# POWER.net
KiCad netlist of a schematic drawn in Altium Designer
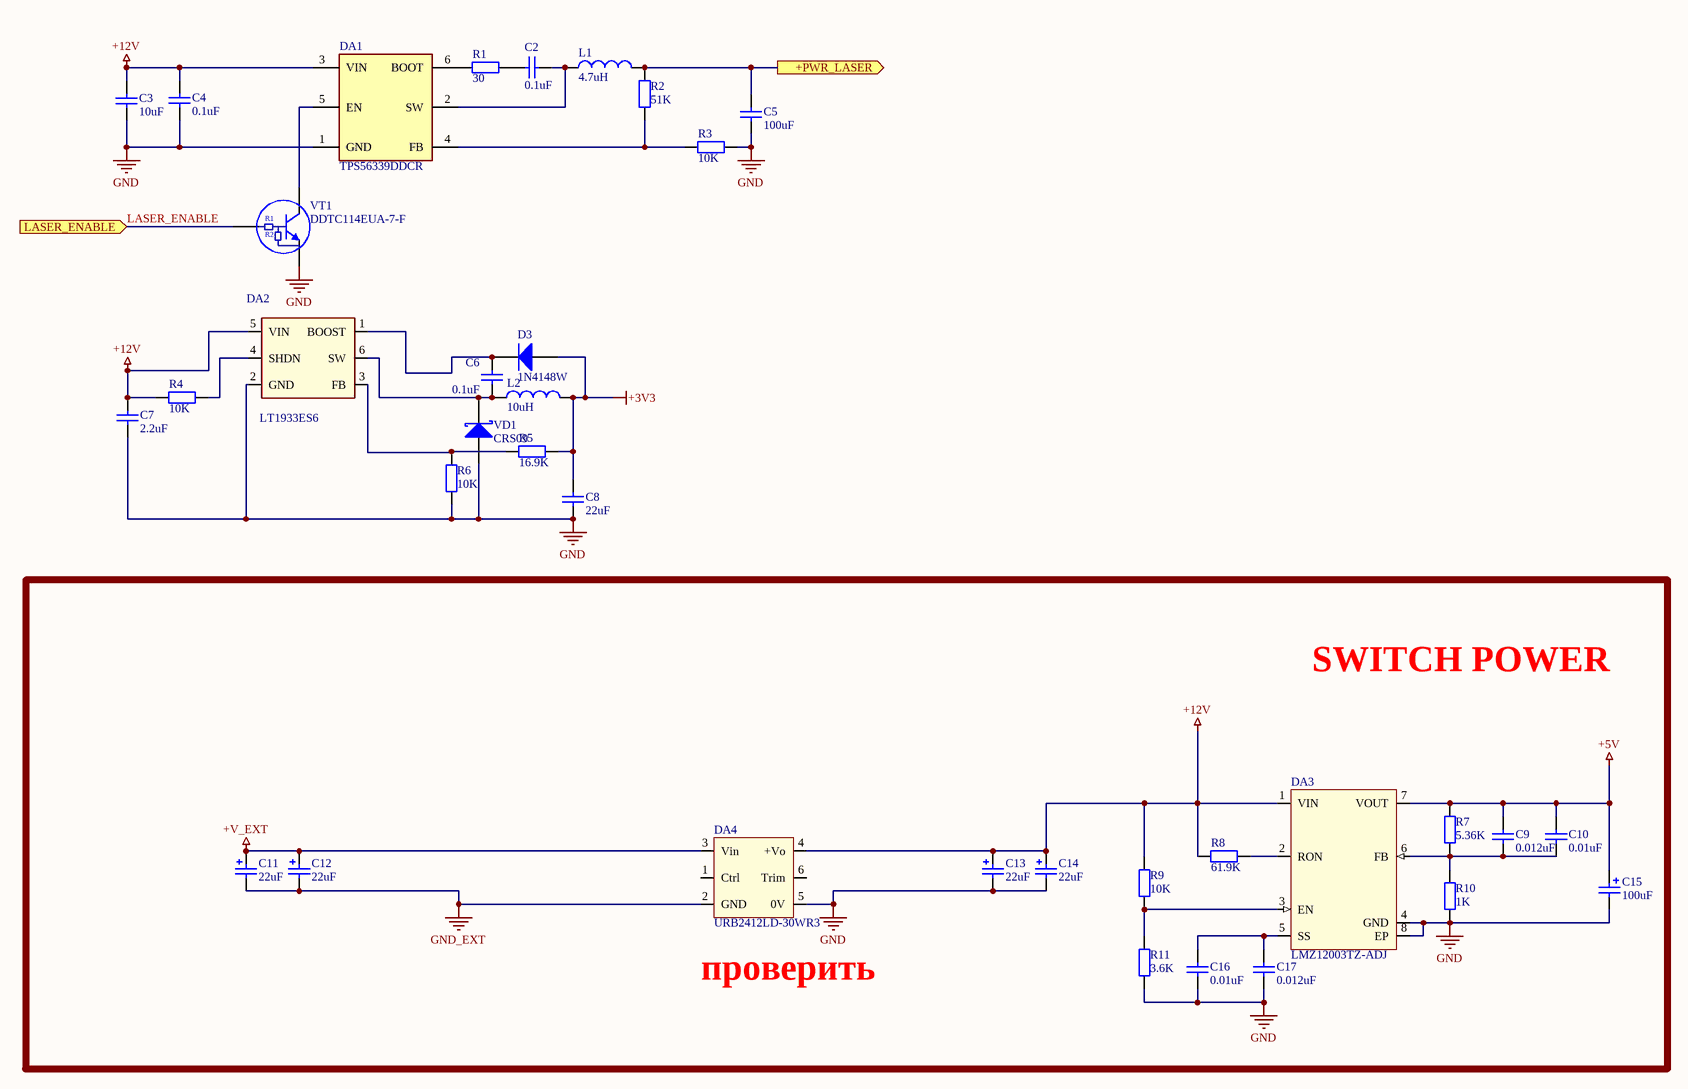
[diagram p0: POWER.SchDoc]

(export (version "E")
  (design (tool "Eeschema 10.0.6"))
  (components
    (comp (ref "C2")
      (value "0.1uF")
      (footprint "C0603")
      (description "Ceramic Capacitor")
      (fields (field (name "Comment") "C0603-0.1uF-50V-X7R"))
      (libsource (lib "Capacitors") (part "C0603-0.1uF-50V-X7R"))
    )
    (comp (ref "C3")
      (value "10uF")
      (footprint "C1210")
      (description "Ceramic Capacitor")
      (fields (field (name "Comment") "C1210-10uF-50V-X7R"))
      (libsource (lib "Capacitors") (part "C1210-10uF-50V-X7R"))
    )
    (comp (ref "C4")
      (value "0.1uF")
      (footprint "C0603")
      (description "Ceramic Capacitor")
      (fields (field (name "Comment") "C0603-0.1uF-50V-X7R"))
      (libsource (lib "Capacitors") (part "C0603-0.1uF-50V-X7R"))
    )
    (comp (ref "C5")
      (value "100uF")
      (footprint "C1206")
      (description "Ceramic Capacitor")
      (fields (field (name "Comment") "C1206-100uF-10V-X5R"))
      (libsource (lib "Capacitors") (part "C1206-100uF-10V-X5R"))
    )
    (comp (ref "C6")
      (value "0.1uF")
      (footprint "C0603")
      (description "Ceramic Capacitor")
      (fields (field (name "Comment") "C0603-0.1uF-50V-X7R"))
      (libsource (lib "Capacitors_SpekrtAT") (part "C0603-0.1uF-50V-X7R"))
    )
    (comp (ref "C7")
      (value "2.2uF")
      (footprint "C1206")
      (description "Ceramic Capacitor")
      (fields (field (name "Comment") "C1206-2.2uF-50V-X7R"))
      (libsource (lib "Capacitors") (part "C1206-2.2uF-50V-X7R"))
    )
    (comp (ref "C8")
      (value "22uF")
      (footprint "C0805")
      (description "Ceramic Capacitor")
      (fields (field (name "Comment") "C0805-22uF-10V-X5R"))
      (libsource (lib "Capacitors_SpekrtAT") (part "C0805-22uF-10V-X5R"))
    )
    (comp (ref "C9")
      (value "0.012uF")
      (footprint "C0603")
      (description "Ceramic Capacitor")
      (fields (field (name "Comment") "C0603-0.012uF-50V-X7R"))
      (libsource (lib "Capacitors_SpekrtAT") (part "C0603-0.012uF-50V-X7R"))
    )
    (comp (ref "C10")
      (value "0.01uF")
      (footprint "C0603")
      (description "Ceramic Capacitor")
      (fields (field (name "Comment") "C0603-0.01uF-50V-X7R"))
      (libsource (lib "Capacitors_SpekrtAT") (part "C0603-0.01uF-50V-X7R"))
    )
    (comp (ref "C11")
      (value "22uF")
      (footprint "CTD")
      (description "Tantalum Capacitor")
      (fields (field (name "Comment") "CTD-22uF-35V"))
      (libsource (lib "Capacitors_SpekrtAT") (part "CTD-22uF-35V"))
    )
    (comp (ref "C12")
      (value "22uF")
      (footprint "CTD")
      (description "Tantalum Capacitor")
      (fields (field (name "Comment") "CTD-22uF-35V"))
      (libsource (lib "Capacitors_SpekrtAT") (part "CTD-22uF-35V"))
    )
    (comp (ref "C13")
      (value "22uF")
      (footprint "CTD")
      (description "Tantalum Capacitor")
      (fields (field (name "Comment") "CTD-22uF-35V"))
      (libsource (lib "Capacitors_SpekrtAT") (part "CTD-22uF-35V"))
    )
    (comp (ref "C14")
      (value "22uF")
      (footprint "CTD")
      (description "Tantalum Capacitor")
      (fields (field (name "Comment") "CTD-22uF-35V"))
      (libsource (lib "Capacitors_SpekrtAT") (part "CTD-22uF-35V"))
    )
    (comp (ref "C15")
      (value "100uF")
      (footprint "CTD")
      (description "Tantalum Capacitor")
      (fields (field (name "Comment") "CTD-100uF-16V"))
      (libsource (lib "Capacitors_SpekrtAT") (part "CTD-100uF-16V"))
    )
    (comp (ref "C16")
      (value "0.01uF")
      (footprint "C0603")
      (description "Ceramic Capacitor")
      (fields (field (name "Comment") "C0603-0.01uF-50V-X7R"))
      (libsource (lib "Capacitors_SpekrtAT") (part "C0603-0.01uF-50V-X7R"))
    )
    (comp (ref "C17")
      (value "0.012uF")
      (footprint "C0603")
      (description "Ceramic Capacitor")
      (fields (field (name "Comment") "C0603-0.012uF-50V-X7R"))
      (libsource (lib "Capacitors_SpekrtAT") (part "C0603-0.012uF-50V-X7R"))
    )
    (comp (ref "D3")
      (value "1N4148W")
      (footprint "SOD323")
      (description "Diode")
      (libsource (lib "Diodes_SpekrtAT") (part "1N4148W"))
    )
    (comp (ref "DA1")
      (value "TPS56339DDCR")
      (footprint "SOT23-6")
      (description "4.5-V to 24-V Input, 3-A Output Synchronous Buck Converter")
      (libsource (lib "ICs") (part "TPS56339DDCR"))
    )
    (comp (ref "DA2")
      (value "LT1933ES6")
      (footprint "SOT23-6")
      (description "PWM step-down DC/DC\r\nconverter")
      (libsource (lib "ICs") (part "LT1933ES6"))
    )
    (comp (ref "DA3")
      (value "LMZ12003TZ-ADJ")
      (footprint "TZA07A")
      (libsource (lib "ICs") (part "LMZ12003TZ-ADJ"))
    )
    (comp (ref "DA4")
      (value "URB2412LD-30WR3")
      (footprint "URB2412LD-30WR3")
      (description "DC/DC Converter")
      (libsource (lib "ICs") (part "URB2412LD-30WR3"))
    )
    (comp (ref "L1")
      (value "4.7uH")
      (footprint "CDRH8D43")
      (description "Inductor")
      (fields (field (name "Comment") "CDRH8D43NP-4R7NC"))
      (libsource (lib "Inductors") (part "CDRH8D43NP-4R7NC"))
    )
    (comp (ref "L2")
      (value "10uH")
      (footprint "VLCF4020T")
      (description "Inductor")
      (fields (field (name "Comment") "VLCF4020T-100MR85"))
      (libsource (lib "Inductors") (part "VLCF4020T-100MR85"))
    )
    (comp (ref "R1")
      (value "30")
      (footprint "R0603")
      (description "Chip Resistor")
      (fields (field (name "Comment") "R0603-30-1%"))
      (libsource (lib "Resistors") (part "R0603-30-1%"))
    )
    (comp (ref "R2")
      (value "51K")
      (footprint "R0603")
      (description "Chip Resistor")
      (fields (field (name "Comment") "R0603-51K-1%"))
      (libsource (lib "Resistors") (part "R0603-51K-1%"))
    )
    (comp (ref "R3")
      (value "10K")
      (footprint "R0603")
      (description "Chip Resistor")
      (fields (field (name "Comment") "R0603-10K-1%"))
      (libsource (lib "Resistors") (part "R0603-10K-1%"))
    )
    (comp (ref "R4")
      (value "10K")
      (footprint "R0603")
      (description "Chip Resistor")
      (fields (field (name "Comment") "R0603-10K-1%"))
      (libsource (lib "") (part "R0603-10K-1%_1"))
    )
    (comp (ref "R5")
      (value "16.9K")
      (footprint "R0603")
      (description "Chip Resistor")
      (fields (field (name "Comment") "R0603-16.9K-1%"))
      (libsource (lib "Resistors") (part "R0603-16.9K-1%"))
    )
    (comp (ref "R6")
      (value "10K")
      (footprint "R0603")
      (description "Chip Resistor")
      (fields (field (name "Comment") "R0603-10K-1%"))
      (libsource (lib "") (part "R0603-10K-1%_1"))
    )
    (comp (ref "R7")
      (value "5.36K")
      (footprint "R0603")
      (description "Chip Resistor")
      (fields (field (name "Comment") "R0603-5.36K-1%"))
      (libsource (lib "Resistors_SpekrtAT") (part "R0603-5.36K-1%"))
    )
    (comp (ref "R8")
      (value "61.9K")
      (footprint "R0603")
      (description "Chip Resistor")
      (fields (field (name "Comment") "R0603-61.9K-1%"))
      (libsource (lib "Resistors_SpekrtAT") (part "R0603-61.9K-1%"))
    )
    (comp (ref "R9")
      (value "10K")
      (footprint "R0603")
      (description "Chip Resistor")
      (fields (field (name "Comment") "R0603-10K-1%"))
      (libsource (lib "Resistors_SpekrtAT") (part "R0603-10K-1%"))
    )
    (comp (ref "R10")
      (value "1K")
      (footprint "R0603")
      (description "Chip Resistor")
      (fields (field (name "Comment") "R0603-1K-1%"))
      (libsource (lib "Resistors") (part "R0603-1K-1%"))
    )
    (comp (ref "R11")
      (value "3.6K")
      (footprint "R0603")
      (description "Chip Resistor")
      (fields (field (name "Comment") "R0603-3.6K-1%"))
      (libsource (lib "Resistors_SpekrtAT") (part "R0603-3.6K-1%"))
    )
    (comp (ref "VD1")
      (value "CRS09")
      (footprint "SFLAT")
      (description "Diode Schottky")
      (libsource (lib "Diodes_SpekrtAT") (part "CRS09(TE85L,Q,M)"))
    )
    (comp (ref "VT1")
      (value "DDTC114EUA-7-F")
      (footprint "SOT323")
      (description "NPN")
      (libsource (lib "Transistors") (part "DDTC114EUA-7-F"))
    )
  )
  (nets
    (net (code "1") (name "+3V3") (class "Default")
      (node (ref "C8") (pin "2") (pinfunction "2_2") (pintype "passive"))
      (node (ref "D3") (pin "1") (pinfunction "A_1") (pintype "passive"))
      (node (ref "L2") (pin "2") (pinfunction "2_2") (pintype "passive"))
      (node (ref "R5") (pin "2") (pinfunction "2_2") (pintype "passive"))
    )
    (net (code "2") (name "+5V") (class "Default")
      (node (ref "C10") (pin "2") (pinfunction "2_2") (pintype "passive"))
      (node (ref "C15") (pin "1") (pinfunction "1_1") (pintype "passive"))
      (node (ref "C9") (pin "2") (pinfunction "2_2") (pintype "passive"))
      (node (ref "DA3") (pin "7") (pinfunction "VOUT_7") (pintype "power_in"))
      (node (ref "R7") (pin "2") (pinfunction "2_2") (pintype "passive"))
    )
    (net (code "3") (name "+12V") (class "Default")
      (node (ref "C13") (pin "1") (pinfunction "1_1") (pintype "passive"))
      (node (ref "C14") (pin "1") (pinfunction "1_1") (pintype "passive"))
      (node (ref "C3") (pin "2") (pinfunction "2_2") (pintype "passive"))
      (node (ref "C4") (pin "1") (pinfunction "1_1") (pintype "passive"))
      (node (ref "C7") (pin "2") (pinfunction "2_2") (pintype "passive"))
      (node (ref "DA1") (pin "3") (pinfunction "VIN_3") (pintype "passive"))
      (node (ref "DA2") (pin "5") (pinfunction "VIN_5") (pintype "passive"))
      (node (ref "DA3") (pin "1") (pinfunction "VIN_1") (pintype "power_in"))
      (node (ref "DA4") (pin "4") (pinfunction "+Vo_4") (pintype "passive"))
      (node (ref "R4") (pin "2") (pinfunction "2_2") (pintype "passive"))
      (node (ref "R8") (pin "1") (pinfunction "1_1") (pintype "passive"))
      (node (ref "R9") (pin "2") (pinfunction "2_2") (pintype "passive"))
    )
    (net (code "4") (name "+V_EXT") (class "Default")
      (node (ref "C11") (pin "1") (pinfunction "1_1") (pintype "passive"))
      (node (ref "C12") (pin "1") (pinfunction "1_1") (pintype "passive"))
      (node (ref "DA4") (pin "3") (pinfunction "Vin_3") (pintype "passive"))
    )
    (net (code "5") (name "/+PWR_LASER") (class "Default")
      (node (ref "C5") (pin "2") (pinfunction "2_2") (pintype "passive"))
      (node (ref "L1") (pin "2") (pinfunction "2_2") (pintype "passive"))
      (node (ref "R2") (pin "2") (pinfunction "2_2") (pintype "passive"))
    )
    (net (code "6") (name "/LASER_ENABLE") (class "Default")
      (node (ref "VT1") (pin "1") (pinfunction "B_1") (pintype "passive"))
    )
    (net (code "7") (name "GND") (class "Default")
      (node (ref "C13") (pin "2") (pinfunction "2_2") (pintype "passive"))
      (node (ref "C14") (pin "2") (pinfunction "2_2") (pintype "passive"))
      (node (ref "C15") (pin "2") (pinfunction "2_2") (pintype "passive"))
      (node (ref "C16") (pin "1") (pinfunction "1_1") (pintype "passive"))
      (node (ref "C17") (pin "1") (pinfunction "1_1") (pintype "passive"))
      (node (ref "C3") (pin "1") (pinfunction "1_1") (pintype "passive"))
      (node (ref "C4") (pin "2") (pinfunction "2_2") (pintype "passive"))
      (node (ref "C5") (pin "1") (pinfunction "1_1") (pintype "passive"))
      (node (ref "C7") (pin "1") (pinfunction "1_1") (pintype "passive"))
      (node (ref "C8") (pin "1") (pinfunction "1_1") (pintype "passive"))
      (node (ref "DA1") (pin "1") (pinfunction "GND_1") (pintype "passive"))
      (node (ref "DA2") (pin "2") (pinfunction "GND_2") (pintype "passive"))
      (node (ref "DA3") (pin "4") (pinfunction "GND_4") (pintype "power_in"))
      (node (ref "DA3") (pin "8") (pinfunction "EP_8") (pintype "power_in"))
      (node (ref "DA4") (pin "5") (pinfunction "0V_5") (pintype "passive"))
      (node (ref "R10") (pin "1") (pinfunction "1_1") (pintype "passive"))
      (node (ref "R11") (pin "1") (pinfunction "1_1") (pintype "passive"))
      (node (ref "R3") (pin "1") (pinfunction "1_1") (pintype "passive"))
      (node (ref "R6") (pin "1") (pinfunction "1_1") (pintype "passive"))
      (node (ref "VD1") (pin "1") (pinfunction "A_1") (pintype "passive"))
      (node (ref "VT1") (pin "2") (pinfunction "E_2") (pintype "passive"))
    )
    (net (code "8") (name "GND_EXT") (class "Default")
      (node (ref "C11") (pin "2") (pinfunction "2_2") (pintype "passive"))
      (node (ref "C12") (pin "2") (pinfunction "2_2") (pintype "passive"))
      (node (ref "DA4") (pin "2") (pinfunction "GND_2") (pintype "passive"))
    )
    (net (code "9") (name "Net-(C2-Pad2)") (class "Default")
      (node (ref "C2") (pin "2") (pinfunction "2_2") (pintype "passive"))
      (node (ref "R1") (pin "2") (pinfunction "2_2") (pintype "passive"))
    )
    (net (code "10") (name "Net-(D3-K)") (class "Default")
      (node (ref "C6") (pin "2") (pinfunction "2_2") (pintype "passive"))
      (node (ref "D3") (pin "2") (pinfunction "K_2") (pintype "passive"))
      (node (ref "DA2") (pin "1") (pinfunction "BOOST_1") (pintype "passive"))
    )
    (net (code "11") (name "Net-(DA1-BOOT)") (class "Default")
      (node (ref "DA1") (pin "6") (pinfunction "BOOT_6") (pintype "passive"))
      (node (ref "R1") (pin "1") (pinfunction "1_1") (pintype "passive"))
    )
    (net (code "12") (name "Net-(DA1-EN)") (class "Default")
      (node (ref "DA1") (pin "5") (pinfunction "EN_5") (pintype "passive"))
      (node (ref "VT1") (pin "3") (pinfunction "C_3") (pintype "passive"))
    )
    (net (code "13") (name "Net-(DA1-FB)") (class "Default")
      (node (ref "DA1") (pin "4") (pinfunction "FB_4") (pintype "passive"))
      (node (ref "R2") (pin "1") (pinfunction "1_1") (pintype "passive"))
      (node (ref "R3") (pin "2") (pinfunction "2_2") (pintype "passive"))
    )
    (net (code "14") (name "Net-(DA1-SW)") (class "Default")
      (node (ref "C2") (pin "1") (pinfunction "1_1") (pintype "passive"))
      (node (ref "DA1") (pin "2") (pinfunction "SW_2") (pintype "passive"))
      (node (ref "L1") (pin "1") (pinfunction "1_1") (pintype "passive"))
    )
    (net (code "15") (name "Net-(DA2-FB)") (class "Default")
      (node (ref "DA2") (pin "3") (pinfunction "FB_3") (pintype "passive"))
      (node (ref "R5") (pin "1") (pinfunction "1_1") (pintype "passive"))
      (node (ref "R6") (pin "2") (pinfunction "2_2") (pintype "passive"))
    )
    (net (code "16") (name "Net-(DA2-SHDN)") (class "Default")
      (node (ref "DA2") (pin "4") (pinfunction "SHDN_4") (pintype "passive"))
      (node (ref "R4") (pin "1") (pinfunction "1_1") (pintype "passive"))
    )
    (net (code "17") (name "Net-(DA2-SW)") (class "Default")
      (node (ref "C6") (pin "1") (pinfunction "1_1") (pintype "passive"))
      (node (ref "DA2") (pin "6") (pinfunction "SW_6") (pintype "passive"))
      (node (ref "L2") (pin "1") (pinfunction "1_1") (pintype "passive"))
      (node (ref "VD1") (pin "2") (pinfunction "K_2") (pintype "passive"))
    )
    (net (code "18") (name "Net-(DA3-EN)") (class "Default")
      (node (ref "DA3") (pin "3") (pinfunction "EN_3") (pintype "input"))
      (node (ref "R11") (pin "2") (pinfunction "2_2") (pintype "passive"))
      (node (ref "R9") (pin "1") (pinfunction "1_1") (pintype "passive"))
    )
    (net (code "19") (name "Net-(DA3-FB)") (class "Default")
      (node (ref "C10") (pin "1") (pinfunction "1_1") (pintype "passive"))
      (node (ref "C9") (pin "1") (pinfunction "1_1") (pintype "passive"))
      (node (ref "DA3") (pin "6") (pinfunction "FB_6") (pintype "input"))
      (node (ref "R10") (pin "2") (pinfunction "2_2") (pintype "passive"))
      (node (ref "R7") (pin "1") (pinfunction "1_1") (pintype "passive"))
    )
    (net (code "20") (name "Net-(DA3-RON)") (class "Default")
      (node (ref "DA3") (pin "2") (pinfunction "RON_2") (pintype "passive"))
      (node (ref "R8") (pin "2") (pinfunction "2_2") (pintype "passive"))
    )
    (net (code "21") (name "Net-(DA3-SS)") (class "Default")
      (node (ref "C16") (pin "2") (pinfunction "2_2") (pintype "passive"))
      (node (ref "C17") (pin "2") (pinfunction "2_2") (pintype "passive"))
      (node (ref "DA3") (pin "5") (pinfunction "SS_5") (pintype "passive"))
    )
    (net (code "22") (name "unconnected-(DA4-Ctrl-Pad1)") (class "Default")
      (node (ref "DA4") (pin "1") (pinfunction "Ctrl_1") (pintype "passive"))
    )
    (net (code "23") (name "unconnected-(DA4-Trim-Pad6)") (class "Default")
      (node (ref "DA4") (pin "6") (pinfunction "Trim_6") (pintype "passive"))
    )
  )
)
